# schematic.net
KiCad netlist of a schematic drawn in EAGLE
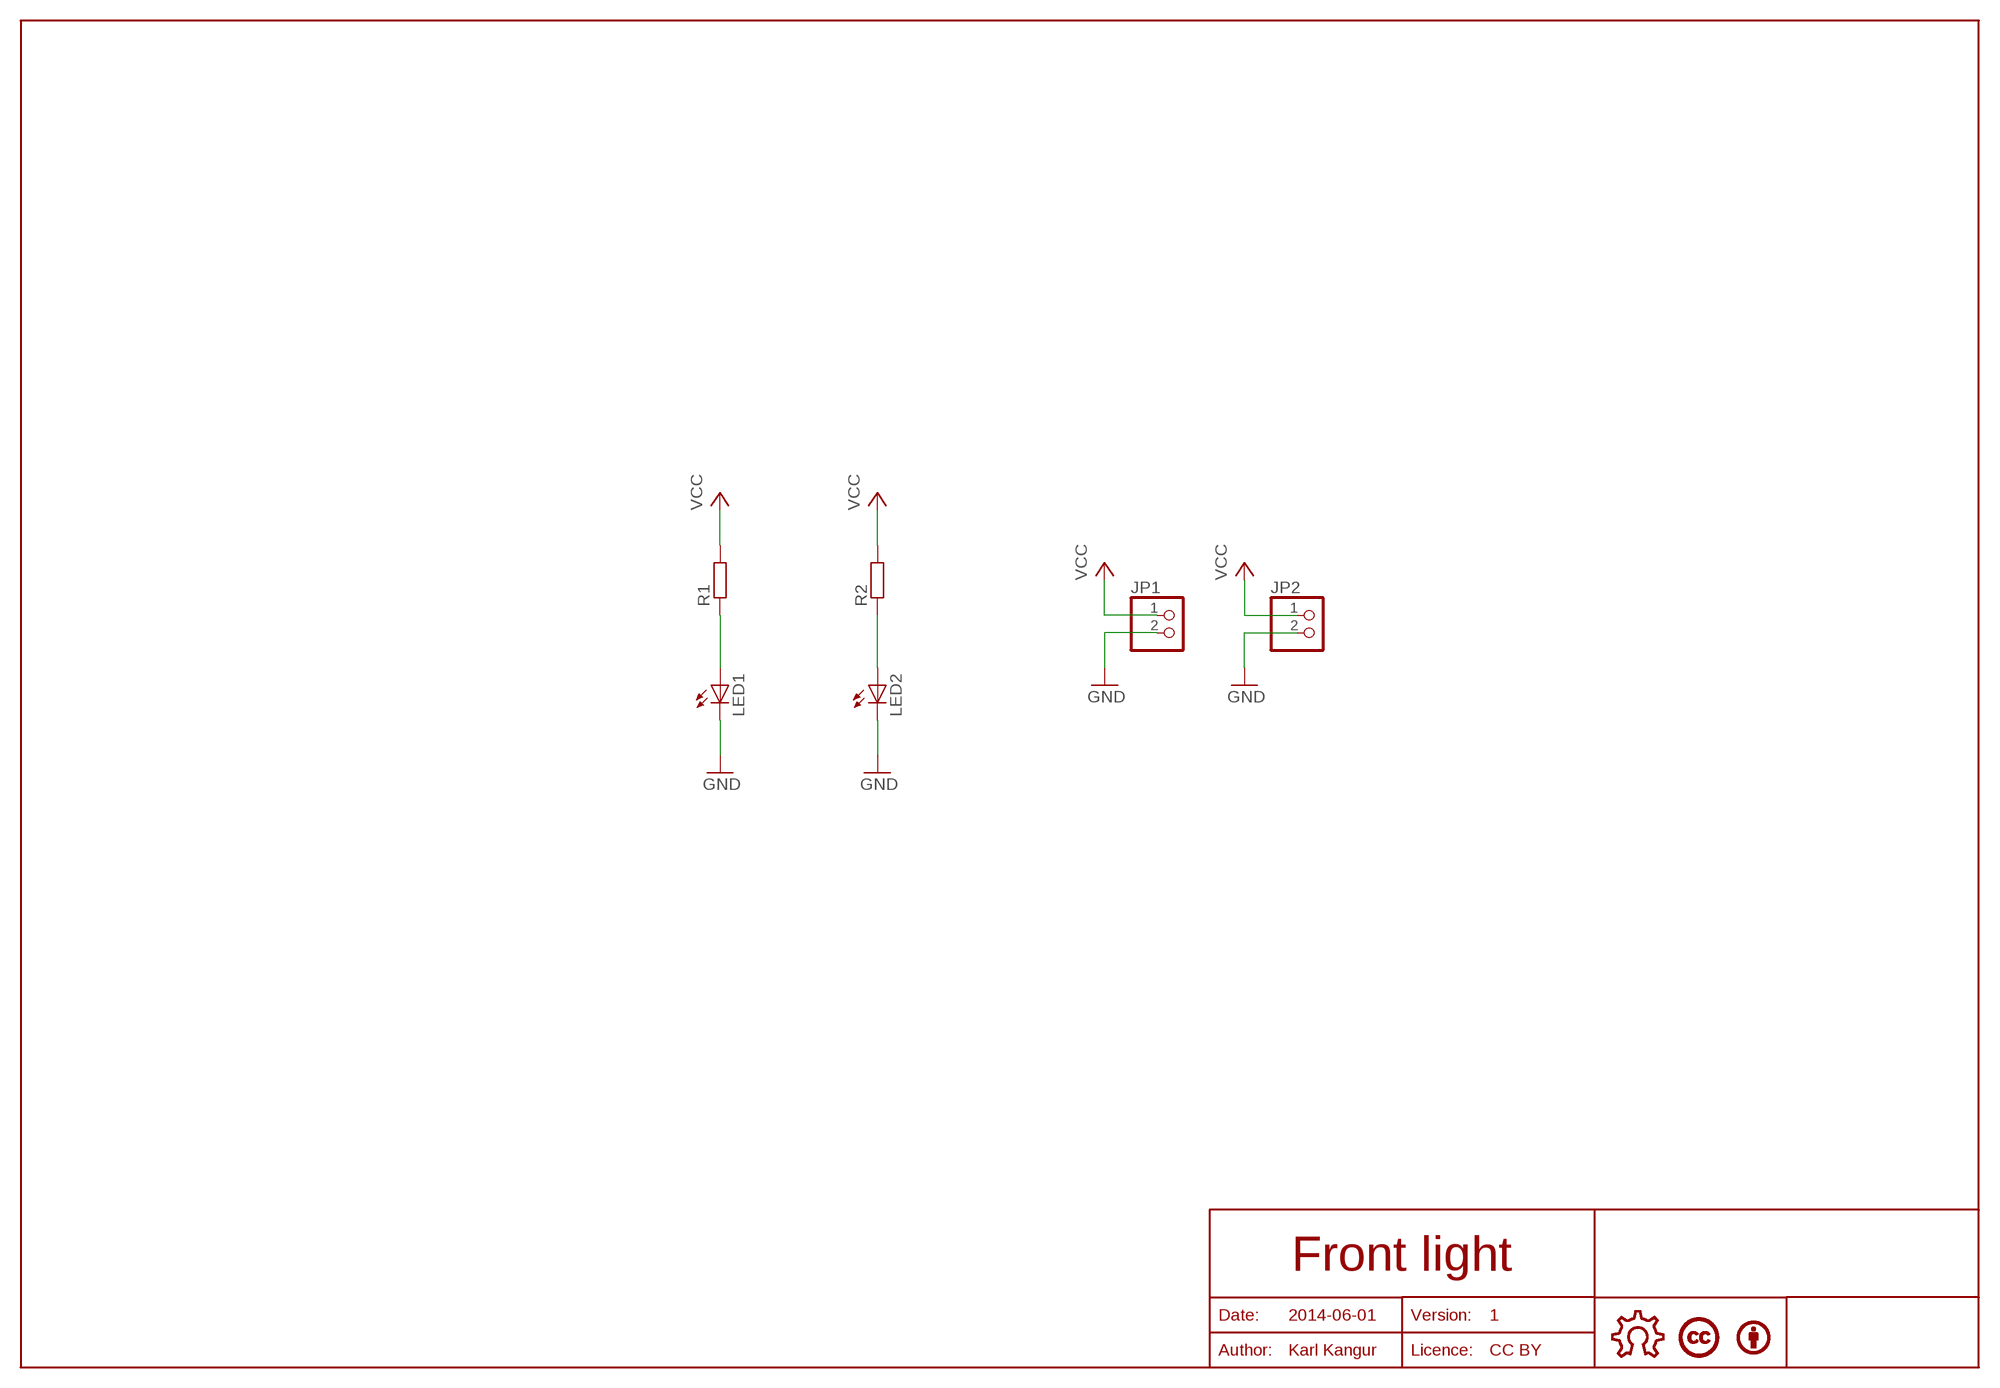
[diagram p0: schematic, sheet 1]

(export (version "E")
  (design (tool "Eeschema 10.0.6"))
  (components
    (comp (ref "BY1")
      (value "BYBOTTOM")
      (footprint "eagle-import:BY")
      (libsource (lib "eagle-import") (part "BYBOTTOM"))
    )
    (comp (ref "JP1")
      (value "PINHD-1X2")
      (footprint "eagle-import:1X02")
      (libsource (lib "eagle-import") (part "PINHD-1X2"))
    )
    (comp (ref "JP2")
      (value "PINHD-1X2")
      (footprint "eagle-import:1X02")
      (libsource (lib "eagle-import") (part "PINHD-1X2"))
    )
    (comp (ref "LED1")
      (value "LED5MM")
      (footprint "eagle-import:LED5MM")
      (libsource (lib "eagle-import") (part "LED5MM"))
    )
    (comp (ref "LED2")
      (value "LED5MM")
      (footprint "eagle-import:LED5MM")
      (libsource (lib "eagle-import") (part "LED5MM"))
    )
    (comp (ref "LICENCE1")
      (value "LICENCECC-BOTTOM")
      (footprint "eagle-import:CREATIVE-COMMONS")
      (libsource (lib "eagle-import") (part "LICENCECC-BOTTOM"))
    )
    (comp (ref "R1")
      (value "R-EU_0207/7")
      (footprint "eagle-import:0207_7")
      (libsource (lib "eagle-import") (part "R-EU_0207/7"))
    )
    (comp (ref "R2")
      (value "R-EU_0207/7")
      (footprint "eagle-import:0207_7")
      (libsource (lib "eagle-import") (part "R-EU_0207/7"))
    )
    (comp (ref "U$10")
      (value "OPEN-HARDWARE-LOGOBOTTOM-SMALL")
      (footprint "eagle-import:OPEN-HARDWARE-BOTTOM-SMALL")
      (libsource (lib "eagle-import") (part "OPEN-HARDWARE-LOGOBOTTOM-SMALL"))
    )
  )
  (nets
    (net (code "1") (name "GND") (class "Default")
      (node (ref "JP1") (pin "2") (pinfunction "2_2") (pintype "passive"))
      (node (ref "JP2") (pin "2") (pinfunction "2_2") (pintype "passive"))
      (node (ref "LED1") (pin "K") (pinfunction "C_K") (pintype "passive"))
      (node (ref "LED2") (pin "K") (pinfunction "C_K") (pintype "passive"))
    )
    (net (code "2") (name "Net-(LED1-PadA)") (class "Default")
      (node (ref "LED1") (pin "A") (pinfunction "A_A") (pintype "passive"))
      (node (ref "R1") (pin "1") (pinfunction "1_1") (pintype "passive"))
    )
    (net (code "3") (name "Net-(LED2-PadA)") (class "Default")
      (node (ref "LED2") (pin "A") (pinfunction "A_A") (pintype "passive"))
      (node (ref "R2") (pin "1") (pinfunction "1_1") (pintype "passive"))
    )
    (net (code "4") (name "VCC") (class "Default")
      (node (ref "JP1") (pin "1") (pinfunction "1_1") (pintype "passive"))
      (node (ref "JP2") (pin "1") (pinfunction "1_1") (pintype "passive"))
      (node (ref "R1") (pin "2") (pinfunction "2_2") (pintype "passive"))
      (node (ref "R2") (pin "2") (pinfunction "2_2") (pintype "passive"))
    )
  )
)
